# PWR.net
KiCad netlist of a schematic drawn in Altium Designer
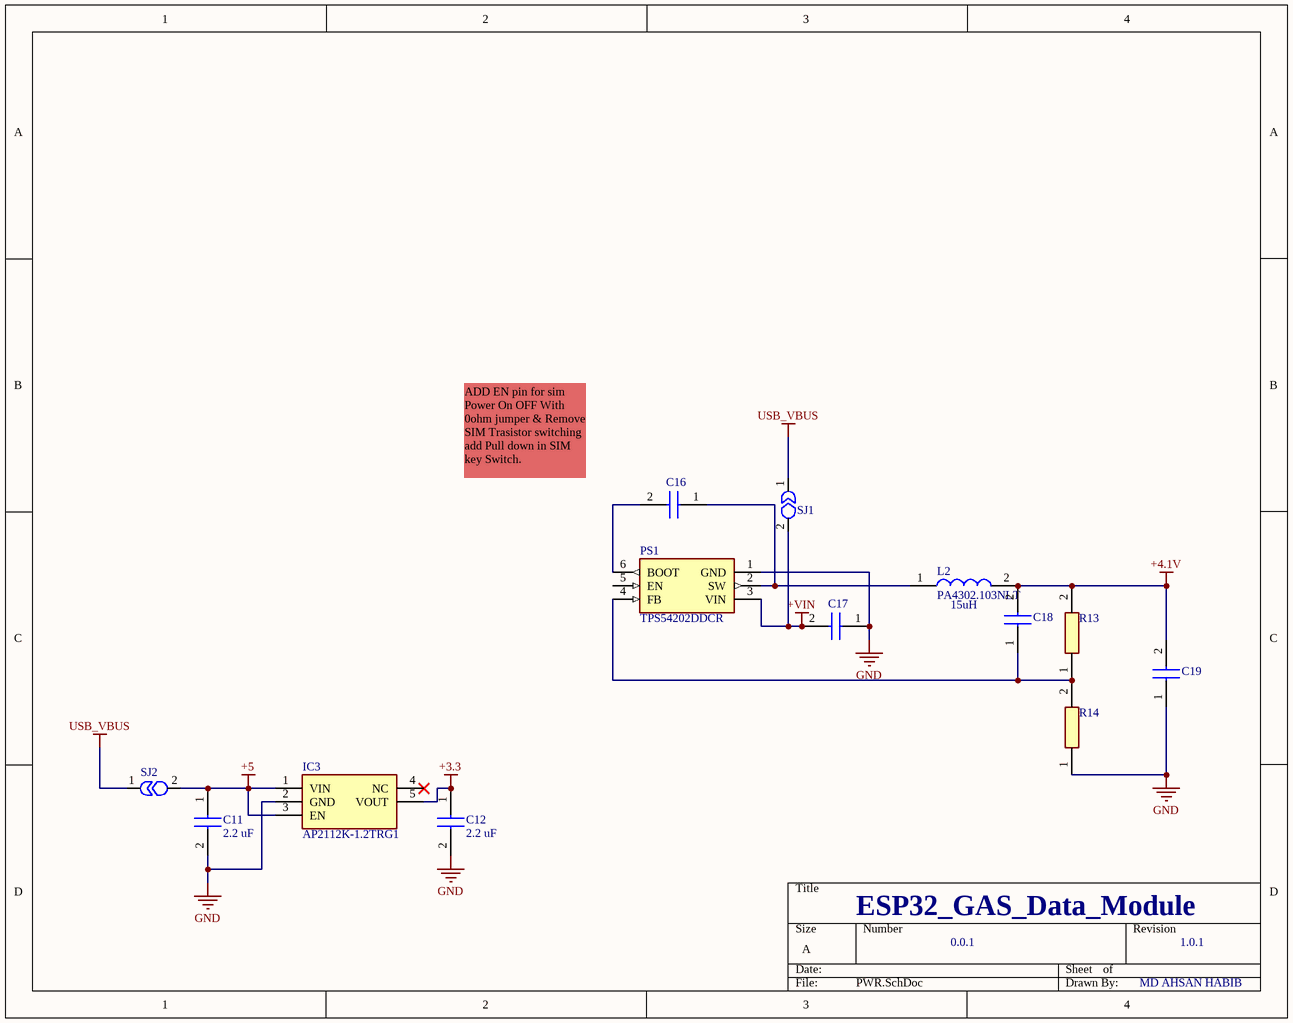
[diagram p0: PWR.SchDoc]

(export (version "E")
  (design (tool "Eeschema 10.0.6"))
  (components
    (comp (ref "C11")
      (value "2.2 uF")
      (footprint "CAP0603")
      (description "Capacitor")
      (fields
        (field (name "MANUFACTURER_PART_NUMBER") "CC0603KRX7R9BB104")
        (field (name "MOUSER PART NUMBER") "603-CC603KRX7R9BB104")
      )
      (libsource (lib "Valve_Controller_Lib") (part "CC0603KRX7R9BB104"))
    )
    (comp (ref "C12")
      (value "2.2 uF")
      (footprint "CAP0603")
      (description "Capacitor")
      (fields
        (field (name "MANUFACTURER_PART_NUMBER") "CC0603KRX7R9BB104")
        (field (name "MOUSER PART NUMBER") "603-CC603KRX7R9BB104")
      )
      (libsource (lib "Valve_Controller_Lib") (part "CC0603KRX7R9BB104"))
    )
    (comp (ref "C16")
      (value "C0805C104M5RAC-TU")
      (footprint "CAPC2012X88N")
      (description "Capacitor")
      (libsource (lib "Valve_Controller_Lib") (part "C0805C104M5RAC-TU"))
    )
    (comp (ref "C17")
      (value "C5750X5R1H106K230KA")
      (footprint "CAP0603")
      (description "Capacitor")
      (fields (field (name "MOUSER PART NUMBER") "810-C5750X5R1H106K"))
      (libsource (lib "Valve_Controller_Lib") (part "C5750X5R1H106K230KA"))
    )
    (comp (ref "C18")
      (value "GRM0335C1E560JA01D")
      (footprint "CAP0603")
      (description "Capacitor")
      (fields (field (name "MOUSER PART NUMBER") "81-GRM0335C1E560JA1D"))
      (libsource (lib "Valve_Controller_Lib") (part "GRM0335C1E560JA01D"))
    )
    (comp (ref "C19")
      (value "GRM32ER61C476KE15L")
      (footprint "CAPC3225X270N")
      (description "Capacitor")
      (fields (field (name "MOUSER PART NUMBER") "81-GRM32ER61C476KE5L"))
      (libsource (lib "Valve_Controller_Lib") (part "GRM32ER61C476KE15L"))
    )
    (comp (ref "IC3")
      (value "AP2112K-1.2TRG1")
      (footprint "SamacSys:SOT95P285X140-5N")
      (description "Integrated Circuit")
      (fields (field (name "MOUSER PART NUMBER") "621-AP2112K-1.2TRG1"))
      (libsource (lib "*") (part "AP2112K-1.2TRG1"))
    )
    (comp (ref "L2")
      (value "PA4302.103NLT")
      (footprint "SamacSys:PA4302103NLT")
      (description "Inductor")
      (fields (field (name "MOUSER PART NUMBER") "673-PA4302.103NLT"))
      (libsource (lib "*") (part "PA4302.103NLT"))
    )
    (comp (ref "PS1")
      (value "TPS54202DDCR")
      (footprint "SOT95P280X110-6N")
      (description "Power Supply")
      (fields (field (name "MOUSER PART NUMBER") "595-TPS54202DDCR"))
      (libsource (lib "Valve_Controller_Lib") (part "TPS54202DDCR"))
    )
    (comp (ref "R13")
      (value "CRCW0402100KFKEDHP")
      (footprint "RES0603")
      (description "Resistor")
      (fields (field (name "MOUSER PART NUMBER") "71-CRCW0402100KFKEDH"))
      (libsource (lib "Valve_Controller_Lib") (part "CRCW0402100KFKEDHP"))
    )
    (comp (ref "R14")
      (value "CRCW040216K9FKEDHP")
      (footprint "RES0603")
      (description "Resistor")
      (fields (field (name "MOUSER PART NUMBER") "71-CRCW040216K9FKEDH"))
      (libsource (lib "Valve_Controller_Lib") (part "CRCW040216K9FKEDHP"))
    )
    (comp (ref "SJ1")
      (value "SOLDER_JUMPER_1206")
      (footprint "JUMP_SOLDER_JUMPER_1206")
      (libsource (lib "") (part "SOLDER_JUMPER_1206_1"))
    )
    (comp (ref "SJ2")
      (value "SOLDER_JUMPER_1206")
      (footprint "JUMP_SOLDER_JUMPER_1206")
      (libsource (lib "SOLDER_JUMPER_1206") (part "SOLDER_JUMPER_1206"))
    )
  )
  (nets
    (net (code "1") (name "+3.3") (class "Default")
      (node (ref "C12") (pin "1") (pinfunction "1_1") (pintype "passive"))
      (node (ref "IC3") (pin "5") (pinfunction "VOUT_5") (pintype "passive"))
    )
    (net (code "2") (name "+4.1V") (class "Default")
      (node (ref "C18") (pin "2") (pinfunction "2_2") (pintype "passive"))
      (node (ref "C19") (pin "2") (pinfunction "2_2") (pintype "passive"))
      (node (ref "L2") (pin "2") (pinfunction "2_2") (pintype "passive"))
      (node (ref "R13") (pin "2") (pinfunction "2_2") (pintype "passive"))
    )
    (net (code "3") (name "+5") (class "Default")
      (node (ref "C11") (pin "1") (pinfunction "1_1") (pintype "passive"))
      (node (ref "IC3") (pin "1") (pinfunction "VIN_1") (pintype "passive"))
      (node (ref "IC3") (pin "3") (pinfunction "EN_3") (pintype "passive"))
      (node (ref "SJ2") (pin "2") (pinfunction "2_2") (pintype "passive"))
    )
    (net (code "4") (name "+VIN") (class "Default")
      (node (ref "C17") (pin "2") (pinfunction "2_2") (pintype "passive"))
      (node (ref "PS1") (pin "3") (pinfunction "VIN_3") (pintype "power_in"))
      (node (ref "SJ1") (pin "2") (pinfunction "2_2") (pintype "passive"))
    )
    (net (code "5") (name "GND") (class "Default")
      (node (ref "C11") (pin "2") (pinfunction "2_2") (pintype "passive"))
      (node (ref "C12") (pin "2") (pinfunction "2_2") (pintype "passive"))
      (node (ref "C17") (pin "1") (pinfunction "1_1") (pintype "passive"))
      (node (ref "C19") (pin "1") (pinfunction "1_1") (pintype "passive"))
      (node (ref "IC3") (pin "2") (pinfunction "GND_2") (pintype "passive"))
      (node (ref "PS1") (pin "1") (pinfunction "GND_1") (pintype "power_in"))
      (node (ref "R14") (pin "1") (pinfunction "1_1") (pintype "passive"))
    )
    (net (code "6") (name "Net-(PS1-BOOT)") (class "Default")
      (node (ref "C16") (pin "2") (pinfunction "2_2") (pintype "passive"))
      (node (ref "PS1") (pin "6") (pinfunction "BOOT_6") (pintype "output"))
    )
    (net (code "7") (name "Net-(PS1-FB)") (class "Default")
      (node (ref "C18") (pin "1") (pinfunction "1_1") (pintype "passive"))
      (node (ref "PS1") (pin "4") (pinfunction "FB_4") (pintype "input"))
      (node (ref "R13") (pin "1") (pinfunction "1_1") (pintype "passive"))
      (node (ref "R14") (pin "2") (pinfunction "2_2") (pintype "passive"))
    )
    (net (code "8") (name "Net-(PS1-SW)") (class "Default")
      (node (ref "C16") (pin "1") (pinfunction "1_1") (pintype "passive"))
      (node (ref "L2") (pin "1") (pinfunction "1_1") (pintype "passive"))
      (node (ref "PS1") (pin "2") (pinfunction "SW_2") (pintype "output"))
    )
    (net (code "9") (name "USB_VBUS") (class "Default")
      (node (ref "SJ1") (pin "1") (pinfunction "1_1") (pintype "passive"))
      (node (ref "SJ2") (pin "1") (pinfunction "1_1") (pintype "passive"))
    )
    (net (code "10") (name "unconnected-(IC3-NC-Pad4)") (class "Default")
      (node (ref "IC3") (pin "4") (pinfunction "NC_4") (pintype "passive+no_connect"))
    )
    (net (code "11") (name "unconnected-(PS1-EN-Pad5)") (class "Default")
      (node (ref "PS1") (pin "5") (pinfunction "EN_5") (pintype "input"))
    )
  )
)
